# Microcontroller.net
KiCad netlist of a schematic drawn in Altium Designer
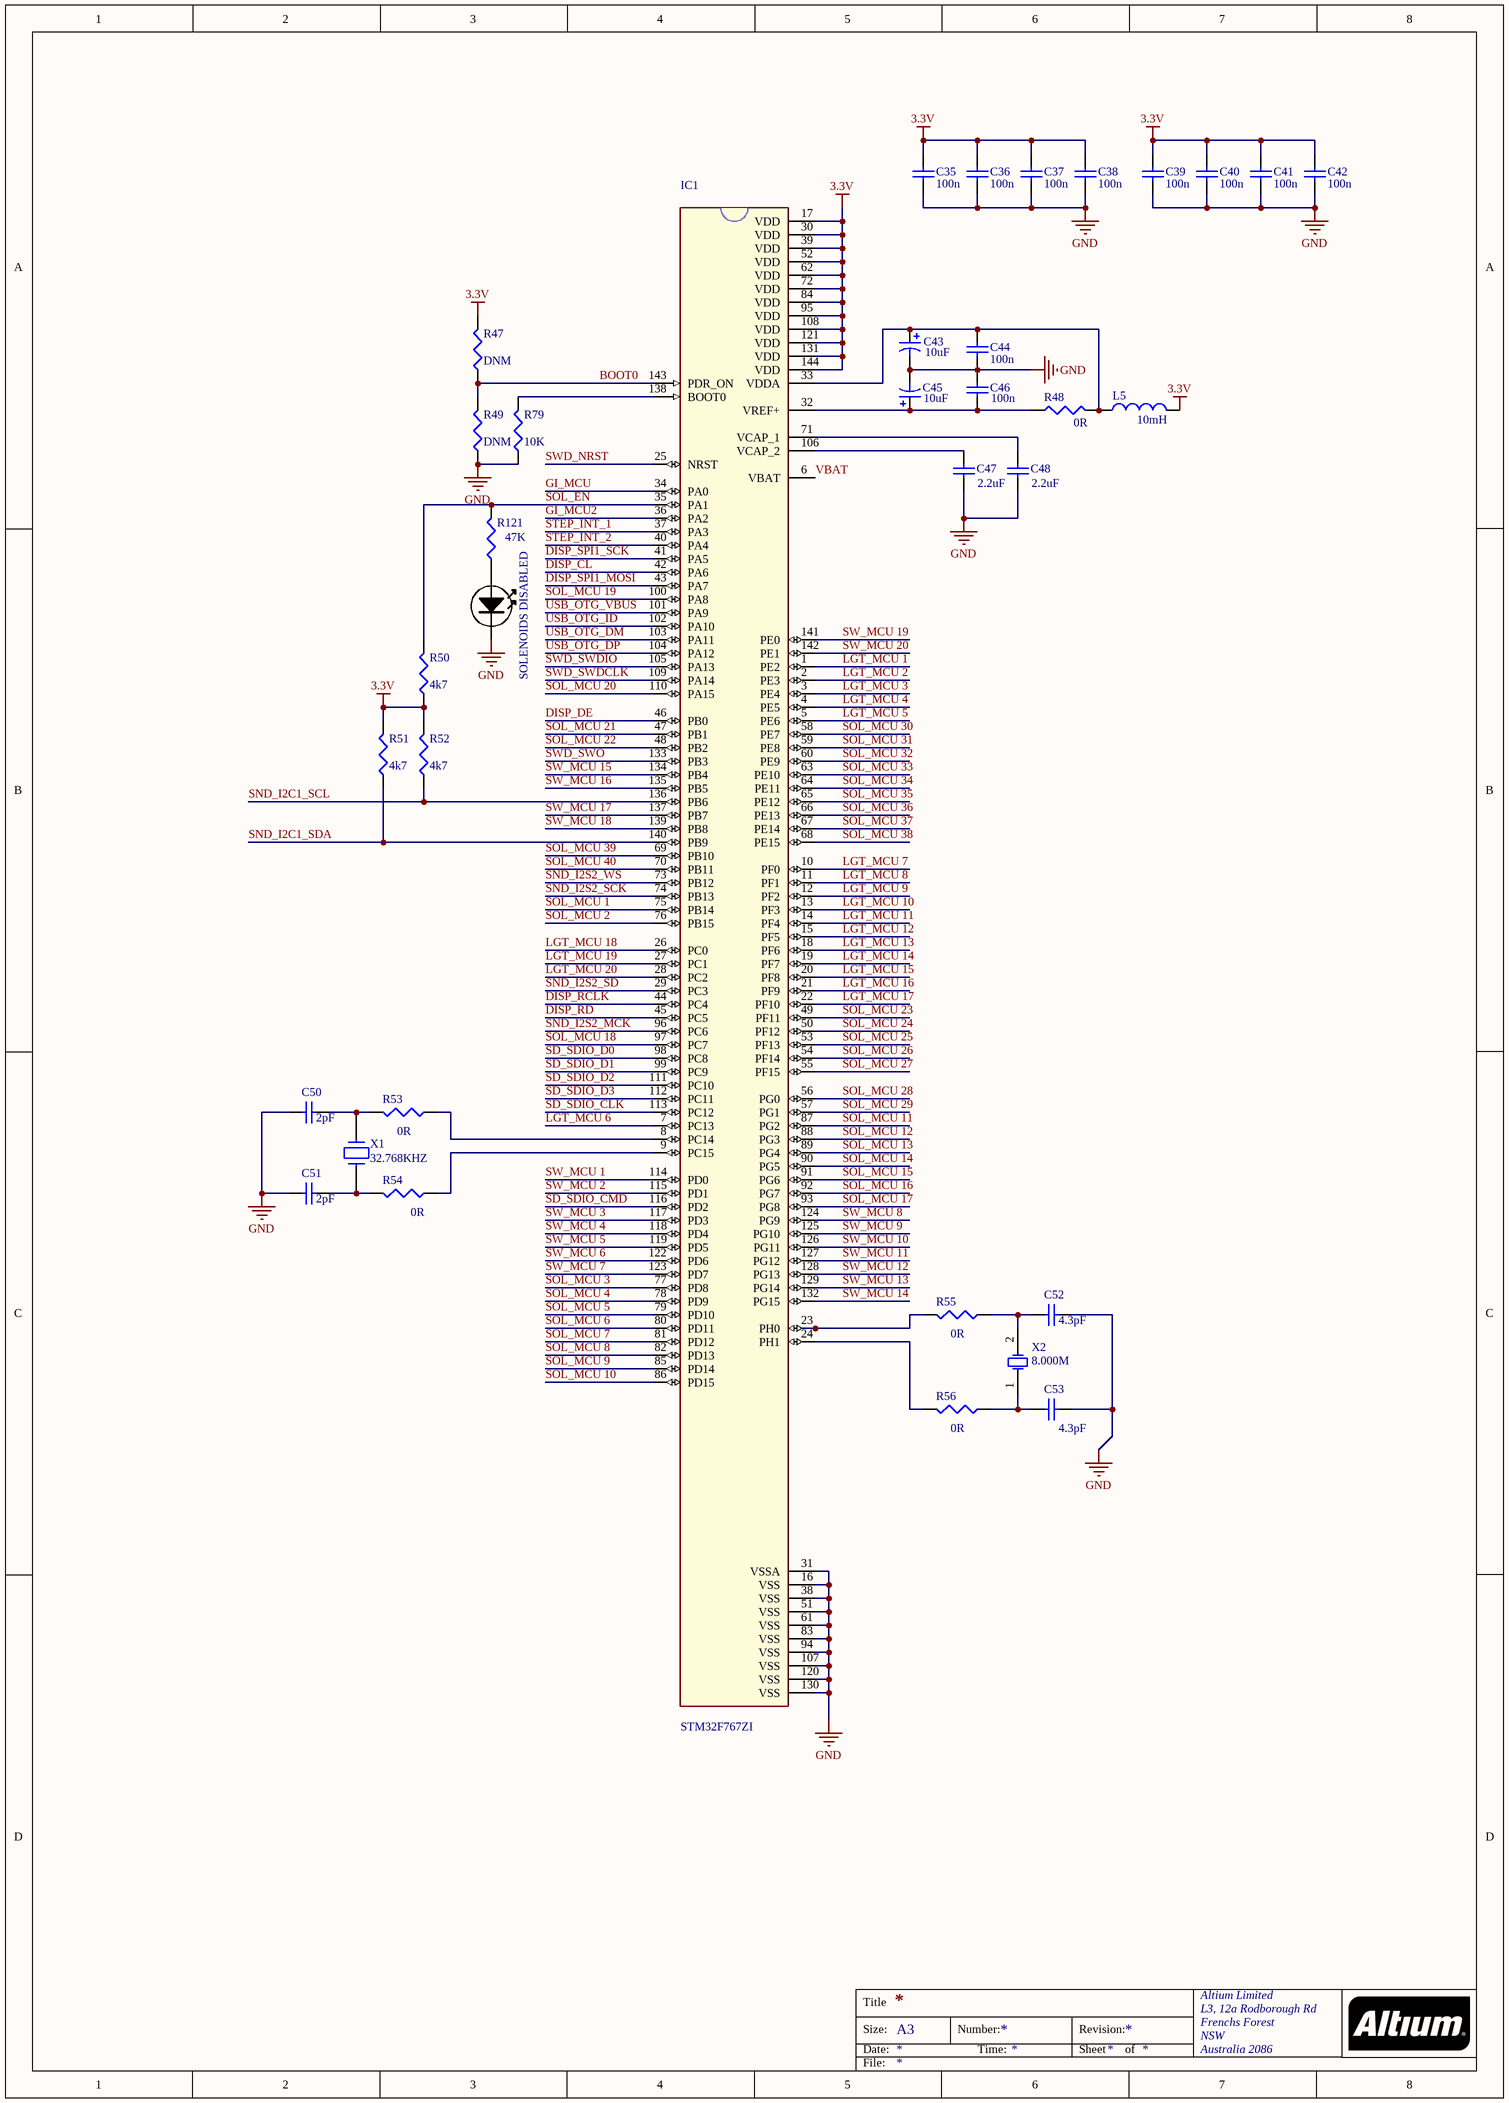
[diagram p0: Microcontroller.SchDoc]

(export (version "E")
  (design (tool "Eeschema 10.0.6"))
  (components
    (comp (ref "C35")
      (value "100n")
      (footprint "0805C-GENERIC")
      (description "Capacitor (Semiconductor SIM Model)")
      (fields (field (name "Comment") "Cap Semi") (field (name "PUBLISHER") "Altium Limited"))
      (libsource (lib "Miscellaneous Devices") (part "Cap Semi"))
    )
    (comp (ref "C36")
      (value "100n")
      (footprint "0805C-GENERIC")
      (description "Capacitor (Semiconductor SIM Model)")
      (fields (field (name "Comment") "Cap Semi") (field (name "PUBLISHER") "Altium Limited"))
      (libsource (lib "Miscellaneous Devices") (part "Cap Semi"))
    )
    (comp (ref "C37")
      (value "100n")
      (footprint "0805C-GENERIC")
      (description "Capacitor (Semiconductor SIM Model)")
      (fields (field (name "Comment") "Cap Semi") (field (name "PUBLISHER") "Altium Limited"))
      (libsource (lib "Miscellaneous Devices") (part "Cap Semi"))
    )
    (comp (ref "C38")
      (value "100n")
      (footprint "0805C-GENERIC")
      (description "Capacitor (Semiconductor SIM Model)")
      (fields (field (name "Comment") "Cap Semi") (field (name "PUBLISHER") "Altium Limited"))
      (libsource (lib "Miscellaneous Devices") (part "Cap Semi"))
    )
    (comp (ref "C39")
      (value "100n")
      (footprint "0805C-GENERIC")
      (description "Capacitor (Semiconductor SIM Model)")
      (fields (field (name "Comment") "Cap Semi") (field (name "PUBLISHER") "Altium Limited"))
      (libsource (lib "Miscellaneous Devices") (part "Cap Semi"))
    )
    (comp (ref "C40")
      (value "100n")
      (footprint "0805C-GENERIC")
      (description "Capacitor (Semiconductor SIM Model)")
      (fields (field (name "Comment") "Cap Semi") (field (name "PUBLISHER") "Altium Limited"))
      (libsource (lib "Miscellaneous Devices") (part "Cap Semi"))
    )
    (comp (ref "C41")
      (value "100n")
      (footprint "0805C-GENERIC")
      (description "Capacitor (Semiconductor SIM Model)")
      (fields (field (name "Comment") "Cap Semi") (field (name "PUBLISHER") "Altium Limited"))
      (libsource (lib "Miscellaneous Devices") (part "Cap Semi"))
    )
    (comp (ref "C42")
      (value "100n")
      (footprint "0805C-GENERIC")
      (description "Capacitor (Semiconductor SIM Model)")
      (fields (field (name "Comment") "Cap Semi") (field (name "PUBLISHER") "Altium Limited"))
      (libsource (lib "Miscellaneous Devices") (part "Cap Semi"))
    )
    (comp (ref "C43")
      (value "10uF")
      (footprint "0805C-GENERIC")
      (description "Polarized Capacitor (Surface Mount)")
      (fields (field (name "Comment") "Cap Pol3") (field (name "PUBLISHER") "Altium Limited"))
      (libsource (lib "Miscellaneous Devices") (part "Cap Pol3"))
    )
    (comp (ref "C44")
      (value "100n")
      (footprint "0805C-GENERIC")
      (description "Capacitor (Semiconductor SIM Model)")
      (fields (field (name "Comment") "Cap Semi") (field (name "PUBLISHER") "Altium Limited"))
      (libsource (lib "Miscellaneous Devices") (part "Cap Semi"))
    )
    (comp (ref "C45")
      (value "10uF")
      (footprint "0805C-GENERIC")
      (description "Polarized Capacitor (Surface Mount)")
      (fields (field (name "Comment") "Cap Pol3") (field (name "PUBLISHER") "Altium Limited"))
      (libsource (lib "Miscellaneous Devices") (part "Cap Pol3"))
    )
    (comp (ref "C46")
      (value "100n")
      (footprint "0805C-GENERIC")
      (description "Capacitor (Semiconductor SIM Model)")
      (fields (field (name "Comment") "Cap Semi") (field (name "PUBLISHER") "Altium Limited"))
      (libsource (lib "Miscellaneous Devices") (part "Cap Semi"))
    )
    (comp (ref "C47")
      (value "2.2uF")
      (footprint "0805C-GENERIC")
      (description "Capacitor (Semiconductor SIM Model)")
      (fields (field (name "Comment") "Cap Semi") (field (name "PUBLISHER") "Altium Limited"))
      (libsource (lib "Miscellaneous Devices") (part "Cap Semi"))
    )
    (comp (ref "C48")
      (value "2.2uF")
      (footprint "0805C-GENERIC")
      (description "Capacitor (Semiconductor SIM Model)")
      (fields (field (name "Comment") "Cap Semi") (field (name "PUBLISHER") "Altium Limited"))
      (libsource (lib "Miscellaneous Devices") (part "Cap Semi"))
    )
    (comp (ref "C50")
      (value "2pF")
      (footprint "0805C-GENERIC")
      (description "Capacitor (Semiconductor SIM Model)")
      (fields (field (name "Comment") "Cap Semi") (field (name "PUBLISHER") "Altium Limited"))
      (libsource (lib "Miscellaneous Devices") (part "Cap Semi"))
    )
    (comp (ref "C51")
      (value "2pF")
      (footprint "0805C-GENERIC")
      (description "Capacitor (Semiconductor SIM Model)")
      (fields (field (name "Comment") "Cap Semi") (field (name "PUBLISHER") "Altium Limited"))
      (libsource (lib "Miscellaneous Devices") (part "Cap Semi"))
    )
    (comp (ref "C52")
      (value "4.3pF")
      (footprint "0805C-GENERIC")
      (description "Capacitor (Semiconductor SIM Model)")
      (fields (field (name "Comment") "Cap Semi") (field (name "PUBLISHER") "Altium Limited"))
      (libsource (lib "Miscellaneous Devices") (part "Cap Semi"))
    )
    (comp (ref "C53")
      (value "4.3pF")
      (footprint "0805C-GENERIC")
      (description "Capacitor (Semiconductor SIM Model)")
      (fields (field (name "Comment") "Cap Semi") (field (name "PUBLISHER") "Altium Limited"))
      (libsource (lib "Miscellaneous Devices") (part "Cap Semi"))
    )
    (comp (ref "IC1")
      (value "STM32F767ZI")
      (footprint "TSQFP50P2200X2200X160-144N")
      (description "IC MCU 32BIT 1MB FLASH 144LQFP")
      (fields (field (name "MP") "STM32F407ZGT6") (field (name "MF") "STMicroelectronics"))
      (libsource (lib "ST") (part "STM32F407ZGT6"))
    )
    (comp (ref "L5")
      (value "10mH")
      (footprint "0805FB-GENERIC")
      (description "Inductor")
      (fields (field (name "PUBLISHER") "Altium Limited"))
      (libsource (lib "Miscellaneous Devices") (part "Inductor"))
    )
    (comp (ref "R47")
      (value "DNM")
      (footprint "0805R-GENERIC")
      (description "Resistor")
      (fields (field (name "Comment") "Res3") (field (name "PUBLISHER") "Altium Limited"))
      (libsource (lib "Miscellaneous Devices") (part "Res3"))
    )
    (comp (ref "R48")
      (value "0R")
      (footprint "0805R-GENERIC")
      (description "Resistor")
      (fields (field (name "Comment") "Res3") (field (name "PUBLISHER") "Altium Limited"))
      (libsource (lib "Miscellaneous Devices") (part "Res3"))
    )
    (comp (ref "R49")
      (value "DNM")
      (footprint "0805R-GENERIC")
      (description "Resistor")
      (fields (field (name "Comment") "Res3") (field (name "PUBLISHER") "Altium Limited"))
      (libsource (lib "Miscellaneous Devices") (part "Res3"))
    )
    (comp (ref "R50")
      (value "4k7")
      (footprint "0805R-GENERIC")
      (description "Resistor")
      (fields (field (name "Comment") "Res3") (field (name "PUBLISHER") "Altium Limited"))
      (libsource (lib "Miscellaneous Devices") (part "Res3"))
    )
    (comp (ref "R51")
      (value "4k7")
      (footprint "0805R-GENERIC")
      (description "Resistor")
      (fields (field (name "Comment") "Res3") (field (name "PUBLISHER") "Altium Limited"))
      (libsource (lib "Miscellaneous Devices") (part "Res3"))
    )
    (comp (ref "R52")
      (value "4k7")
      (footprint "0805R-GENERIC")
      (description "Resistor")
      (fields (field (name "Comment") "Res3") (field (name "PUBLISHER") "Altium Limited"))
      (libsource (lib "Miscellaneous Devices") (part "Res3"))
    )
    (comp (ref "R53")
      (value "0R")
      (footprint "0805R-GENERIC")
      (description "Resistor")
      (fields (field (name "Comment") "Res3") (field (name "PUBLISHER") "Altium Limited"))
      (libsource (lib "Miscellaneous Devices") (part "Res3"))
    )
    (comp (ref "R54")
      (value "0R")
      (footprint "0805R-GENERIC")
      (description "Resistor")
      (fields (field (name "Comment") "Res3") (field (name "PUBLISHER") "Altium Limited"))
      (libsource (lib "Miscellaneous Devices") (part "Res3"))
    )
    (comp (ref "R55")
      (value "0R")
      (footprint "0805R-GENERIC")
      (description "Resistor")
      (fields (field (name "Comment") "Res3") (field (name "PUBLISHER") "Altium Limited"))
      (libsource (lib "Miscellaneous Devices") (part "Res3"))
    )
    (comp (ref "R56")
      (value "0R")
      (footprint "0805R-GENERIC")
      (description "Resistor")
      (fields (field (name "Comment") "Res3") (field (name "PUBLISHER") "Altium Limited"))
      (libsource (lib "Miscellaneous Devices") (part "Res3"))
    )
    (comp (ref "R79")
      (value "10K")
      (footprint "0805R-GENERIC")
      (description "Resistor")
      (fields (field (name "Comment") "Res3") (field (name "PUBLISHER") "Altium Limited"))
      (libsource (lib "Miscellaneous Devices") (part "Res3"))
    )
    (comp (ref "R121")
      (value "47K")
      (footprint "0805R-GENERIC")
      (description "Resistor")
      (fields (field (name "Comment") "Res3") (field (name "PUBLISHER") "Altium Limited"))
      (libsource (lib "Miscellaneous Devices") (part "Res3"))
    )
    (comp (ref "SOLENOIDS DISABLED")
      (value "LED-RED-3MM")
      (footprint "LED-3MM-RED")
      (libsource (lib "vh_altium_library") (part "LED-RED-3MM"))
    )
    (comp (ref "X1")
      (value "32.768KHZ")
      (footprint "XTAL_2SM_3R2X1R5")
      (description "Crystal")
      (libsource (lib "MB1167") (part "CRYSTAL_32K"))
    )
    (comp (ref "X2")
      (value "8.000M")
      (footprint "OSC_2SM_3R2x2R5")
      (description "Crystal Oscillator")
      (fields (field (name "PUBLISHER") "Altium Limited"))
      (libsource (lib "MB963_1") (part "XTAL"))
    )
  )
  (nets
    (net (code "1") (name "/BOOT0") (class "Default")
      (node (ref "IC1") (pin "143") (pinfunction "PDR_ON_143") (pintype "input"))
      (node (ref "R47") (pin "1") (pinfunction "1_1") (pintype "passive"))
      (node (ref "R49") (pin "2") (pinfunction "2_2") (pintype "passive"))
    )
    (net (code "2") (name "/DISP_CL") (class "Default")
      (node (ref "IC1") (pin "42") (pinfunction "PA6_42") (pintype "bidirectional"))
    )
    (net (code "3") (name "/DISP_DE") (class "Default")
      (node (ref "IC1") (pin "46") (pinfunction "PB0_46") (pintype "bidirectional"))
    )
    (net (code "4") (name "/DISP_RCLK") (class "Default")
      (node (ref "IC1") (pin "44") (pinfunction "PC4_44") (pintype "bidirectional"))
    )
    (net (code "5") (name "/DISP_RD") (class "Default")
      (node (ref "IC1") (pin "45") (pinfunction "PC5_45") (pintype "bidirectional"))
    )
    (net (code "6") (name "/DISP_SPI1_MOSI") (class "Default")
      (node (ref "IC1") (pin "43") (pinfunction "PA7_43") (pintype "bidirectional"))
    )
    (net (code "7") (name "/DISP_SPI1_SCK") (class "Default")
      (node (ref "IC1") (pin "41") (pinfunction "PA5_41") (pintype "bidirectional"))
    )
    (net (code "8") (name "/GI_MCU") (class "Default")
      (node (ref "IC1") (pin "34") (pinfunction "PA0_34") (pintype "bidirectional"))
    )
    (net (code "9") (name "/GI_MCU2") (class "Default")
      (node (ref "IC1") (pin "36") (pinfunction "PA2_36") (pintype "bidirectional"))
    )
    (net (code "10") (name "/LGT_MCU 1") (class "Default")
      (node (ref "IC1") (pin "1") (pinfunction "PE2_1") (pintype "bidirectional"))
    )
    (net (code "11") (name "/LGT_MCU 2") (class "Default")
      (node (ref "IC1") (pin "2") (pinfunction "PE3_2") (pintype "bidirectional"))
    )
    (net (code "12") (name "/LGT_MCU 3") (class "Default")
      (node (ref "IC1") (pin "3") (pinfunction "PE4_3") (pintype "bidirectional"))
    )
    (net (code "13") (name "/LGT_MCU 4") (class "Default")
      (node (ref "IC1") (pin "4") (pinfunction "PE5_4") (pintype "bidirectional"))
    )
    (net (code "14") (name "/LGT_MCU 5") (class "Default")
      (node (ref "IC1") (pin "5") (pinfunction "PE6_5") (pintype "bidirectional"))
    )
    (net (code "15") (name "/LGT_MCU 6") (class "Default")
      (node (ref "IC1") (pin "7") (pinfunction "PC13_7") (pintype "bidirectional"))
    )
    (net (code "16") (name "/LGT_MCU 7") (class "Default")
      (node (ref "IC1") (pin "10") (pinfunction "PF0_10") (pintype "bidirectional"))
    )
    (net (code "17") (name "/LGT_MCU 8") (class "Default")
      (node (ref "IC1") (pin "11") (pinfunction "PF1_11") (pintype "bidirectional"))
    )
    (net (code "18") (name "/LGT_MCU 9") (class "Default")
      (node (ref "IC1") (pin "12") (pinfunction "PF2_12") (pintype "bidirectional"))
    )
    (net (code "19") (name "/LGT_MCU 10") (class "Default")
      (node (ref "IC1") (pin "13") (pinfunction "PF3_13") (pintype "bidirectional"))
    )
    (net (code "20") (name "/LGT_MCU 11") (class "Default")
      (node (ref "IC1") (pin "14") (pinfunction "PF4_14") (pintype "bidirectional"))
    )
    (net (code "21") (name "/LGT_MCU 12") (class "Default")
      (node (ref "IC1") (pin "15") (pinfunction "PF5_15") (pintype "bidirectional"))
    )
    (net (code "22") (name "/LGT_MCU 13") (class "Default")
      (node (ref "IC1") (pin "18") (pinfunction "PF6_18") (pintype "bidirectional"))
    )
    (net (code "23") (name "/LGT_MCU 14") (class "Default")
      (node (ref "IC1") (pin "19") (pinfunction "PF7_19") (pintype "bidirectional"))
    )
    (net (code "24") (name "/LGT_MCU 15") (class "Default")
      (node (ref "IC1") (pin "20") (pinfunction "PF8_20") (pintype "bidirectional"))
    )
    (net (code "25") (name "/LGT_MCU 16") (class "Default")
      (node (ref "IC1") (pin "21") (pinfunction "PF9_21") (pintype "bidirectional"))
    )
    (net (code "26") (name "/LGT_MCU 17") (class "Default")
      (node (ref "IC1") (pin "22") (pinfunction "PF10_22") (pintype "bidirectional"))
    )
    (net (code "27") (name "/LGT_MCU 18") (class "Default")
      (node (ref "IC1") (pin "26") (pinfunction "PC0_26") (pintype "bidirectional"))
    )
    (net (code "28") (name "/LGT_MCU 19") (class "Default")
      (node (ref "IC1") (pin "27") (pinfunction "PC1_27") (pintype "bidirectional"))
    )
    (net (code "29") (name "/LGT_MCU 20") (class "Default")
      (node (ref "IC1") (pin "28") (pinfunction "PC2_28") (pintype "bidirectional"))
    )
    (net (code "30") (name "/SD_SDIO_CLK") (class "Default")
      (node (ref "IC1") (pin "113") (pinfunction "PC12_113") (pintype "bidirectional"))
    )
    (net (code "31") (name "/SD_SDIO_CMD") (class "Default")
      (node (ref "IC1") (pin "116") (pinfunction "PD2_116") (pintype "bidirectional"))
    )
    (net (code "32") (name "/SD_SDIO_D0") (class "Default")
      (node (ref "IC1") (pin "98") (pinfunction "PC8_98") (pintype "bidirectional"))
    )
    (net (code "33") (name "/SD_SDIO_D1") (class "Default")
      (node (ref "IC1") (pin "99") (pinfunction "PC9_99") (pintype "bidirectional"))
    )
    (net (code "34") (name "/SD_SDIO_D2") (class "Default")
      (node (ref "IC1") (pin "111") (pinfunction "PC10_111") (pintype "bidirectional"))
    )
    (net (code "35") (name "/SD_SDIO_D3") (class "Default")
      (node (ref "IC1") (pin "112") (pinfunction "PC11_112") (pintype "bidirectional"))
    )
    (net (code "36") (name "/SND_I2C1_SCL") (class "Default")
      (node (ref "IC1") (pin "136") (pinfunction "PB6_136") (pintype "bidirectional"))
      (node (ref "R52") (pin "1") (pinfunction "1_1") (pintype "passive"))
    )
    (net (code "37") (name "/SND_I2C1_SDA") (class "Default")
      (node (ref "IC1") (pin "140") (pinfunction "PB9_140") (pintype "bidirectional"))
      (node (ref "R51") (pin "1") (pinfunction "1_1") (pintype "passive"))
    )
    (net (code "38") (name "/SND_I2S2_MCK") (class "Default")
      (node (ref "IC1") (pin "96") (pinfunction "PC6_96") (pintype "bidirectional"))
    )
    (net (code "39") (name "/SND_I2S2_SCK") (class "Default")
      (node (ref "IC1") (pin "74") (pinfunction "PB13_74") (pintype "bidirectional"))
    )
    (net (code "40") (name "/SND_I2S2_SD") (class "Default")
      (node (ref "IC1") (pin "29") (pinfunction "PC3_29") (pintype "bidirectional"))
    )
    (net (code "41") (name "/SND_I2S2_WS") (class "Default")
      (node (ref "IC1") (pin "73") (pinfunction "PB12_73") (pintype "bidirectional"))
    )
    (net (code "42") (name "/SOL_EN") (class "Default")
      (node (ref "IC1") (pin "35") (pinfunction "PA1_35") (pintype "bidirectional"))
      (node (ref "R121") (pin "2") (pinfunction "2_2") (pintype "passive"))
      (node (ref "R50") (pin "2") (pinfunction "2_2") (pintype "passive"))
    )
    (net (code "43") (name "/SOL_MCU 1") (class "Default")
      (node (ref "IC1") (pin "75") (pinfunction "PB14_75") (pintype "bidirectional"))
    )
    (net (code "44") (name "/SOL_MCU 2") (class "Default")
      (node (ref "IC1") (pin "76") (pinfunction "PB15_76") (pintype "bidirectional"))
    )
    (net (code "45") (name "/SOL_MCU 3") (class "Default")
      (node (ref "IC1") (pin "77") (pinfunction "PD8_77") (pintype "bidirectional"))
    )
    (net (code "46") (name "/SOL_MCU 4") (class "Default")
      (node (ref "IC1") (pin "78") (pinfunction "PD9_78") (pintype "bidirectional"))
    )
    (net (code "47") (name "/SOL_MCU 5") (class "Default")
      (node (ref "IC1") (pin "79") (pinfunction "PD10_79") (pintype "bidirectional"))
    )
    (net (code "48") (name "/SOL_MCU 6") (class "Default")
      (node (ref "IC1") (pin "80") (pinfunction "PD11_80") (pintype "bidirectional"))
    )
    (net (code "49") (name "/SOL_MCU 7") (class "Default")
      (node (ref "IC1") (pin "81") (pinfunction "PD12_81") (pintype "bidirectional"))
    )
    (net (code "50") (name "/SOL_MCU 8") (class "Default")
      (node (ref "IC1") (pin "82") (pinfunction "PD13_82") (pintype "bidirectional"))
    )
    (net (code "51") (name "/SOL_MCU 9") (class "Default")
      (node (ref "IC1") (pin "85") (pinfunction "PD14_85") (pintype "bidirectional"))
    )
    (net (code "52") (name "/SOL_MCU 10") (class "Default")
      (node (ref "IC1") (pin "86") (pinfunction "PD15_86") (pintype "bidirectional"))
    )
    (net (code "53") (name "/SOL_MCU 11") (class "Default")
      (node (ref "IC1") (pin "87") (pinfunction "PG2_87") (pintype "bidirectional"))
    )
    (net (code "54") (name "/SOL_MCU 12") (class "Default")
      (node (ref "IC1") (pin "88") (pinfunction "PG3_88") (pintype "bidirectional"))
    )
    (net (code "55") (name "/SOL_MCU 13") (class "Default")
      (node (ref "IC1") (pin "89") (pinfunction "PG4_89") (pintype "bidirectional"))
    )
    (net (code "56") (name "/SOL_MCU 14") (class "Default")
      (node (ref "IC1") (pin "90") (pinfunction "PG5_90") (pintype "bidirectional"))
    )
    (net (code "57") (name "/SOL_MCU 15") (class "Default")
      (node (ref "IC1") (pin "91") (pinfunction "PG6_91") (pintype "bidirectional"))
    )
    (net (code "58") (name "/SOL_MCU 16") (class "Default")
      (node (ref "IC1") (pin "92") (pinfunction "PG7_92") (pintype "bidirectional"))
    )
    (net (code "59") (name "/SOL_MCU 17") (class "Default")
      (node (ref "IC1") (pin "93") (pinfunction "PG8_93") (pintype "bidirectional"))
    )
    (net (code "60") (name "/SOL_MCU 18") (class "Default")
      (node (ref "IC1") (pin "97") (pinfunction "PC7_97") (pintype "bidirectional"))
    )
    (net (code "61") (name "/SOL_MCU 19") (class "Default")
      (node (ref "IC1") (pin "100") (pinfunction "PA8_100") (pintype "bidirectional"))
    )
    (net (code "62") (name "/SOL_MCU 20") (class "Default")
      (node (ref "IC1") (pin "110") (pinfunction "PA15_110") (pintype "bidirectional"))
    )
    (net (code "63") (name "/SOL_MCU 21") (class "Default")
      (node (ref "IC1") (pin "47") (pinfunction "PB1_47") (pintype "bidirectional"))
    )
    (net (code "64") (name "/SOL_MCU 22") (class "Default")
      (node (ref "IC1") (pin "48") (pinfunction "PB2_48") (pintype "bidirectional"))
    )
    (net (code "65") (name "/SOL_MCU 23") (class "Default")
      (node (ref "IC1") (pin "49") (pinfunction "PF11_49") (pintype "bidirectional"))
    )
    (net (code "66") (name "/SOL_MCU 24") (class "Default")
      (node (ref "IC1") (pin "50") (pinfunction "PF12_50") (pintype "bidirectional"))
    )
    (net (code "67") (name "/SOL_MCU 25") (class "Default")
      (node (ref "IC1") (pin "53") (pinfunction "PF13_53") (pintype "bidirectional"))
    )
    (net (code "68") (name "/SOL_MCU 26") (class "Default")
      (node (ref "IC1") (pin "54") (pinfunction "PF14_54") (pintype "bidirectional"))
    )
    (net (code "69") (name "/SOL_MCU 27") (class "Default")
      (node (ref "IC1") (pin "55") (pinfunction "PF15_55") (pintype "bidirectional"))
    )
    (net (code "70") (name "/SOL_MCU 28") (class "Default")
      (node (ref "IC1") (pin "56") (pinfunction "PG0_56") (pintype "bidirectional"))
    )
    (net (code "71") (name "/SOL_MCU 29") (class "Default")
      (node (ref "IC1") (pin "57") (pinfunction "PG1_57") (pintype "bidirectional"))
    )
    (net (code "72") (name "/SOL_MCU 30") (class "Default")
      (node (ref "IC1") (pin "58") (pinfunction "PE7_58") (pintype "bidirectional"))
    )
    (net (code "73") (name "/SOL_MCU 31") (class "Default")
      (node (ref "IC1") (pin "59") (pinfunction "PE8_59") (pintype "bidirectional"))
    )
    (net (code "74") (name "/SOL_MCU 32") (class "Default")
      (node (ref "IC1") (pin "60") (pinfunction "PE9_60") (pintype "bidirectional"))
    )
    (net (code "75") (name "/SOL_MCU 33") (class "Default")
      (node (ref "IC1") (pin "63") (pinfunction "PE10_63") (pintype "bidirectional"))
    )
    (net (code "76") (name "/SOL_MCU 34") (class "Default")
      (node (ref "IC1") (pin "64") (pinfunction "PE11_64") (pintype "bidirectional"))
    )
    (net (code "77") (name "/SOL_MCU 35") (class "Default")
      (node (ref "IC1") (pin "65") (pinfunction "PE12_65") (pintype "bidirectional"))
    )
    (net (code "78") (name "/SOL_MCU 36") (class "Default")
      (node (ref "IC1") (pin "66") (pinfunction "PE13_66") (pintype "bidirectional"))
    )
    (net (code "79") (name "/SOL_MCU 37") (class "Default")
      (node (ref "IC1") (pin "67") (pinfunction "PE14_67") (pintype "bidirectional"))
    )
    (net (code "80") (name "/SOL_MCU 38") (class "Default")
      (node (ref "IC1") (pin "68") (pinfunction "PE15_68") (pintype "bidirectional"))
    )
    (net (code "81") (name "/SOL_MCU 39") (class "Default")
      (node (ref "IC1") (pin "69") (pinfunction "PB10_69") (pintype "bidirectional"))
    )
    (net (code "82") (name "/SOL_MCU 40") (class "Default")
      (node (ref "IC1") (pin "70") (pinfunction "PB11_70") (pintype "bidirectional"))
    )
    (net (code "83") (name "/STEP_INT_1") (class "Default")
      (node (ref "IC1") (pin "37") (pinfunction "PA3_37") (pintype "bidirectional"))
    )
    (net (code "84") (name "/STEP_INT_2") (class "Default")
      (node (ref "IC1") (pin "40") (pinfunction "PA4_40") (pintype "bidirectional"))
    )
    (net (code "85") (name "/SWD_NRST") (class "Default")
      (node (ref "IC1") (pin "25") (pinfunction "NRST_25") (pintype "bidirectional"))
    )
    (net (code "86") (name "/SWD_SWDCLK") (class "Default")
      (node (ref "IC1") (pin "109") (pinfunction "PA14_109") (pintype "bidirectional"))
    )
    (net (code "87") (name "/SWD_SWDIO") (class "Default")
      (node (ref "IC1") (pin "105") (pinfunction "PA13_105") (pintype "bidirectional"))
    )
    (net (code "88") (name "/SWD_SWO") (class "Default")
      (node (ref "IC1") (pin "133") (pinfunction "PB3_133") (pintype "bidirectional"))
    )
    (net (code "89") (name "/SW_MCU 1") (class "Default")
      (node (ref "IC1") (pin "114") (pinfunction "PD0_114") (pintype "bidirectional"))
    )
    (net (code "90") (name "/SW_MCU 2") (class "Default")
      (node (ref "IC1") (pin "115") (pinfunction "PD1_115") (pintype "bidirectional"))
    )
    (net (code "91") (name "/SW_MCU 3") (class "Default")
      (node (ref "IC1") (pin "117") (pinfunction "PD3_117") (pintype "bidirectional"))
    )
    (net (code "92") (name "/SW_MCU 4") (class "Default")
      (node (ref "IC1") (pin "118") (pinfunction "PD4_118") (pintype "bidirectional"))
    )
    (net (code "93") (name "/SW_MCU 5") (class "Default")
      (node (ref "IC1") (pin "119") (pinfunction "PD5_119") (pintype "bidirectional"))
    )
    (net (code "94") (name "/SW_MCU 6") (class "Default")
      (node (ref "IC1") (pin "122") (pinfunction "PD6_122") (pintype "bidirectional"))
    )
    (net (code "95") (name "/SW_MCU 7") (class "Default")
      (node (ref "IC1") (pin "123") (pinfunction "PD7_123") (pintype "bidirectional"))
    )
    (net (code "96") (name "/SW_MCU 8") (class "Default")
      (node (ref "IC1") (pin "124") (pinfunction "PG9_124") (pintype "bidirectional"))
    )
    (net (code "97") (name "/SW_MCU 9") (class "Default")
      (node (ref "IC1") (pin "125") (pinfunction "PG10_125") (pintype "bidirectional"))
    )
    (net (code "98") (name "/SW_MCU 10") (class "Default")
      (node (ref "IC1") (pin "126") (pinfunction "PG11_126") (pintype "bidirectional"))
    )
    (net (code "99") (name "/SW_MCU 11") (class "Default")
      (node (ref "IC1") (pin "127") (pinfunction "PG12_127") (pintype "bidirectional"))
    )
    (net (code "100") (name "/SW_MCU 12") (class "Default")
      (node (ref "IC1") (pin "128") (pinfunction "PG13_128") (pintype "bidirectional"))
    )
    (net (code "101") (name "/SW_MCU 13") (class "Default")
      (node (ref "IC1") (pin "129") (pinfunction "PG14_129") (pintype "bidirectional"))
    )
    (net (code "102") (name "/SW_MCU 14") (class "Default")
      (node (ref "IC1") (pin "132") (pinfunction "PG15_132") (pintype "bidirectional"))
    )
    (net (code "103") (name "/SW_MCU 15") (class "Default")
      (node (ref "IC1") (pin "134") (pinfunction "PB4_134") (pintype "bidirectional"))
    )
    (net (code "104") (name "/SW_MCU 16") (class "Default")
      (node (ref "IC1") (pin "135") (pinfunction "PB5_135") (pintype "bidirectional"))
    )
    (net (code "105") (name "/SW_MCU 17") (class "Default")
      (node (ref "IC1") (pin "137") (pinfunction "PB7_137") (pintype "bidirectional"))
    )
    (net (code "106") (name "/SW_MCU 18") (class "Default")
      (node (ref "IC1") (pin "139") (pinfunction "PB8_139") (pintype "bidirectional"))
    )
    (net (code "107") (name "/SW_MCU 19") (class "Default")
      (node (ref "IC1") (pin "141") (pinfunction "PE0_141") (pintype "bidirectional"))
    )
    (net (code "108") (name "/SW_MCU 20") (class "Default")
      (node (ref "IC1") (pin "142") (pinfunction "PE1_142") (pintype "bidirectional"))
    )
    (net (code "109") (name "/USB_OTG_DM") (class "Default")
      (node (ref "IC1") (pin "103") (pinfunction "PA11_103") (pintype "bidirectional"))
    )
    (net (code "110") (name "/USB_OTG_DP") (class "Default")
      (node (ref "IC1") (pin "104") (pinfunction "PA12_104") (pintype "bidirectional"))
    )
    (net (code "111") (name "/USB_OTG_ID") (class "Default")
      (node (ref "IC1") (pin "102") (pinfunction "PA10_102") (pintype "bidirectional"))
    )
    (net (code "112") (name "/USB_OTG_VBUS") (class "Default")
      (node (ref "IC1") (pin "101") (pinfunction "PA9_101") (pintype "bidirectional"))
    )
    (net (code "113") (name "/VBAT") (class "Default")
      (node (ref "IC1") (pin "6") (pinfunction "VBAT_6") (pintype "power_in"))
    )
    (net (code "114") (name "3.3V") (class "Default")
      (node (ref "C35") (pin "2") (pinfunction "2_2") (pintype "passive"))
      (node (ref "C36") (pin "2") (pinfunction "2_2") (pintype "passive"))
      (node (ref "C37") (pin "2") (pinfunction "2_2") (pintype "passive"))
      (node (ref "C38") (pin "2") (pinfunction "2_2") (pintype "passive"))
      (node (ref "C39") (pin "2") (pinfunction "2_2") (pintype "passive"))
      (node (ref "C40") (pin "2") (pinfunction "2_2") (pintype "passive"))
      (node (ref "C41") (pin "2") (pinfunction "2_2") (pintype "passive"))
      (node (ref "C42") (pin "2") (pinfunction "2_2") (pintype "passive"))
      (node (ref "IC1") (pin "108") (pinfunction "VDD_108") (pintype "power_in"))
      (node (ref "IC1") (pin "121") (pinfunction "VDD_121") (pintype "power_in"))
      (node (ref "IC1") (pin "131") (pinfunction "VDD_131") (pintype "power_in"))
      (node (ref "IC1") (pin "144") (pinfunction "VDD_144") (pintype "power_in"))
      (node (ref "IC1") (pin "17") (pinfunction "VDD_17") (pintype "power_in"))
      (node (ref "IC1") (pin "30") (pinfunction "VDD_30") (pintype "power_in"))
      (node (ref "IC1") (pin "39") (pinfunction "VDD_39") (pintype "power_in"))
      (node (ref "IC1") (pin "52") (pinfunction "VDD_52") (pintype "power_in"))
      (node (ref "IC1") (pin "62") (pinfunction "VDD_62") (pintype "power_in"))
      (node (ref "IC1") (pin "72") (pinfunction "VDD_72") (pintype "power_in"))
      (node (ref "IC1") (pin "84") (pinfunction "VDD_84") (pintype "power_in"))
      (node (ref "IC1") (pin "95") (pinfunction "VDD_95") (pintype "power_in"))
      (node (ref "L5") (pin "2") (pinfunction "2_2") (pintype "passive"))
      (node (ref "R47") (pin "2") (pinfunction "2_2") (pintype "passive"))
      (node (ref "R50") (pin "1") (pinfunction "1_1") (pintype "passive"))
      (node (ref "R51") (pin "2") (pinfunction "2_2") (pintype "passive"))
      (node (ref "R52") (pin "2") (pinfunction "2_2") (pintype "passive"))
    )
    (net (code "115") (name "GND") (class "Default")
      (node (ref "C35") (pin "1") (pinfunction "1_1") (pintype "passive"))
      (node (ref "C36") (pin "1") (pinfunction "1_1") (pintype "passive"))
      (node (ref "C37") (pin "1") (pinfunction "1_1") (pintype "passive"))
      (node (ref "C38") (pin "1") (pinfunction "1_1") (pintype "passive"))
      (node (ref "C39") (pin "1") (pinfunction "1_1") (pintype "passive"))
      (node (ref "C40") (pin "1") (pinfunction "1_1") (pintype "passive"))
      (node (ref "C41") (pin "1") (pinfunction "1_1") (pintype "passive"))
      (node (ref "C42") (pin "1") (pinfunction "1_1") (pintype "passive"))
      (node (ref "C43") (pin "2") (pinfunction "2_2") (pintype "passive"))
      (node (ref "C44") (pin "1") (pinfunction "1_1") (pintype "passive"))
      (node (ref "C45") (pin "2") (pinfunction "2_2") (pintype "passive"))
      (node (ref "C46") (pin "2") (pinfunction "2_2") (pintype "passive"))
      (node (ref "C47") (pin "1") (pinfunction "1_1") (pintype "passive"))
      (node (ref "C48") (pin "1") (pinfunction "1_1") (pintype "passive"))
      (node (ref "C50") (pin "1") (pinfunction "1_1") (pintype "passive"))
      (node (ref "C51") (pin "1") (pinfunction "1_1") (pintype "passive"))
      (node (ref "C52") (pin "2") (pinfunction "2_2") (pintype "passive"))
      (node (ref "C53") (pin "2") (pinfunction "2_2") (pintype "passive"))
      (node (ref "IC1") (pin "107") (pinfunction "VSS_107") (pintype "passive"))
      (node (ref "IC1") (pin "120") (pinfunction "VSS_120") (pintype "passive"))
      (node (ref "IC1") (pin "130") (pinfunction "VSS_130") (pintype "passive"))
      (node (ref "IC1") (pin "16") (pinfunction "VSS_16") (pintype "passive"))
      (node (ref "IC1") (pin "31") (pinfunction "VSSA_31") (pintype "passive"))
      (node (ref "IC1") (pin "38") (pinfunction "VSS_38") (pintype "passive"))
      (node (ref "IC1") (pin "51") (pinfunction "VSS_51") (pintype "passive"))
      (node (ref "IC1") (pin "61") (pinfunction "VSS_61") (pintype "passive"))
      (node (ref "IC1") (pin "83") (pinfunction "VSS_83") (pintype "passive"))
      (node (ref "IC1") (pin "94") (pinfunction "VSS_94") (pintype "passive"))
      (node (ref "R49") (pin "1") (pinfunction "1_1") (pintype "passive"))
      (node (ref "R79") (pin "1") (pinfunction "1_1") (pintype "passive"))
      (node (ref "SOLENOIDS DISABLED") (pin "K") (pintype "passive"))
    )
    (net (code "116") (name "Net-(C50-Pad2)") (class "Default")
      (node (ref "C50") (pin "2") (pinfunction "2_2") (pintype "passive"))
      (node (ref "R53") (pin "2") (pinfunction "2_2") (pintype "passive"))
      (node (ref "X1") (pin "2") (pinfunction "2_2") (pintype "passive"))
    )
    (net (code "117") (name "Net-(C51-Pad2)") (class "Default")
      (node (ref "C51") (pin "2") (pinfunction "2_2") (pintype "passive"))
      (node (ref "R54") (pin "2") (pinfunction "2_2") (pintype "passive"))
      (node (ref "X1") (pin "1") (pinfunction "1_1") (pintype "passive"))
    )
    (net (code "118") (name "Net-(IC1-BOOT0)") (class "Default")
      (node (ref "IC1") (pin "138") (pinfunction "BOOT0_138") (pintype "input"))
      (node (ref "R79") (pin "2") (pinfunction "2_2") (pintype "passive"))
    )
    (net (code "119") (name "Net-(IC1-PC14)") (class "Default")
      (node (ref "IC1") (pin "8") (pinfunction "PC14_8") (pintype "bidirectional"))
      (node (ref "R53") (pin "1") (pinfunction "1_1") (pintype "passive"))
    )
    (net (code "120") (name "Net-(IC1-PC15)") (class "Default")
      (node (ref "IC1") (pin "9") (pinfunction "PC15_9") (pintype "bidirectional"))
      (node (ref "R54") (pin "1") (pinfunction "1_1") (pintype "passive"))
    )
    (net (code "121") (name "Net-(IC1-PH0)") (class "Default")
      (node (ref "IC1") (pin "23") (pinfunction "PH0_23") (pintype "bidirectional"))
      (node (ref "R55") (pin "2") (pinfunction "2_2") (pintype "passive"))
    )
    (net (code "122") (name "Net-(IC1-PH1)") (class "Default")
      (node (ref "IC1") (pin "24") (pinfunction "PH1_24") (pintype "bidirectional"))
      (node (ref "R56") (pin "2") (pinfunction "2_2") (pintype "passive"))
    )
    (net (code "123") (name "Net-(IC1-VCAP_1)") (class "Default")
      (node (ref "C48") (pin "2") (pinfunction "2_2") (pintype "passive"))
      (node (ref "IC1") (pin "71") (pinfunction "VCAP_1_71") (pintype "power_in"))
    )
    (net (code "124") (name "Net-(IC1-VCAP_2)") (class "Default")
      (node (ref "C47") (pin "2") (pinfunction "2_2") (pintype "passive"))
      (node (ref "IC1") (pin "106") (pinfunction "VCAP_2_106") (pintype "power_in"))
    )
    (net (code "125") (name "Net-(IC1-VDDA)") (class "Default")
      (node (ref "C43") (pin "1") (pinfunction "1_1") (pintype "passive"))
      (node (ref "C44") (pin "2") (pinfunction "2_2") (pintype "passive"))
      (node (ref "IC1") (pin "33") (pinfunction "VDDA_33") (pintype "power_in"))
      (node (ref "L5") (pin "1") (pinfunction "1_1") (pintype "passive"))
      (node (ref "R48") (pin "2") (pinfunction "2_2") (pintype "passive"))
    )
    (net (code "126") (name "Net-(IC1-VREF+)") (class "Default")
      (node (ref "C45") (pin "1") (pinfunction "1_1") (pintype "passive"))
      (node (ref "C46") (pin "1") (pinfunction "1_1") (pintype "passive"))
      (node (ref "IC1") (pin "32") (pinfunction "VREF+_32") (pintype "power_in"))
      (node (ref "R48") (pin "1") (pinfunction "1_1") (pintype "passive"))
    )
    (net (code "127") (name "Net-(R121-Pad1)") (class "Default")
      (node (ref "R121") (pin "1") (pinfunction "1_1") (pintype "passive"))
      (node (ref "SOLENOIDS DISABLED") (pin "A") (pintype "passive"))
    )
    (net (code "128") (name "Net-(X2-OSC1)") (class "Default")
      (node (ref "C53") (pin "1") (pinfunction "1_1") (pintype "passive"))
      (node (ref "R56") (pin "1") (pinfunction "1_1") (pintype "passive"))
      (node (ref "X2") (pin "1") (pinfunction "OSC1_1") (pintype "passive"))
    )
    (net (code "129") (name "Net-(X2-OSC2)") (class "Default")
      (node (ref "C52") (pin "1") (pinfunction "1_1") (pintype "passive"))
      (node (ref "R55") (pin "1") (pinfunction "1_1") (pintype "passive"))
      (node (ref "X2") (pin "2") (pinfunction "OSC2_2") (pintype "passive"))
    )
  )
)
